# 05-USB-UART.net
KiCad netlist of a schematic drawn in Altium Designer
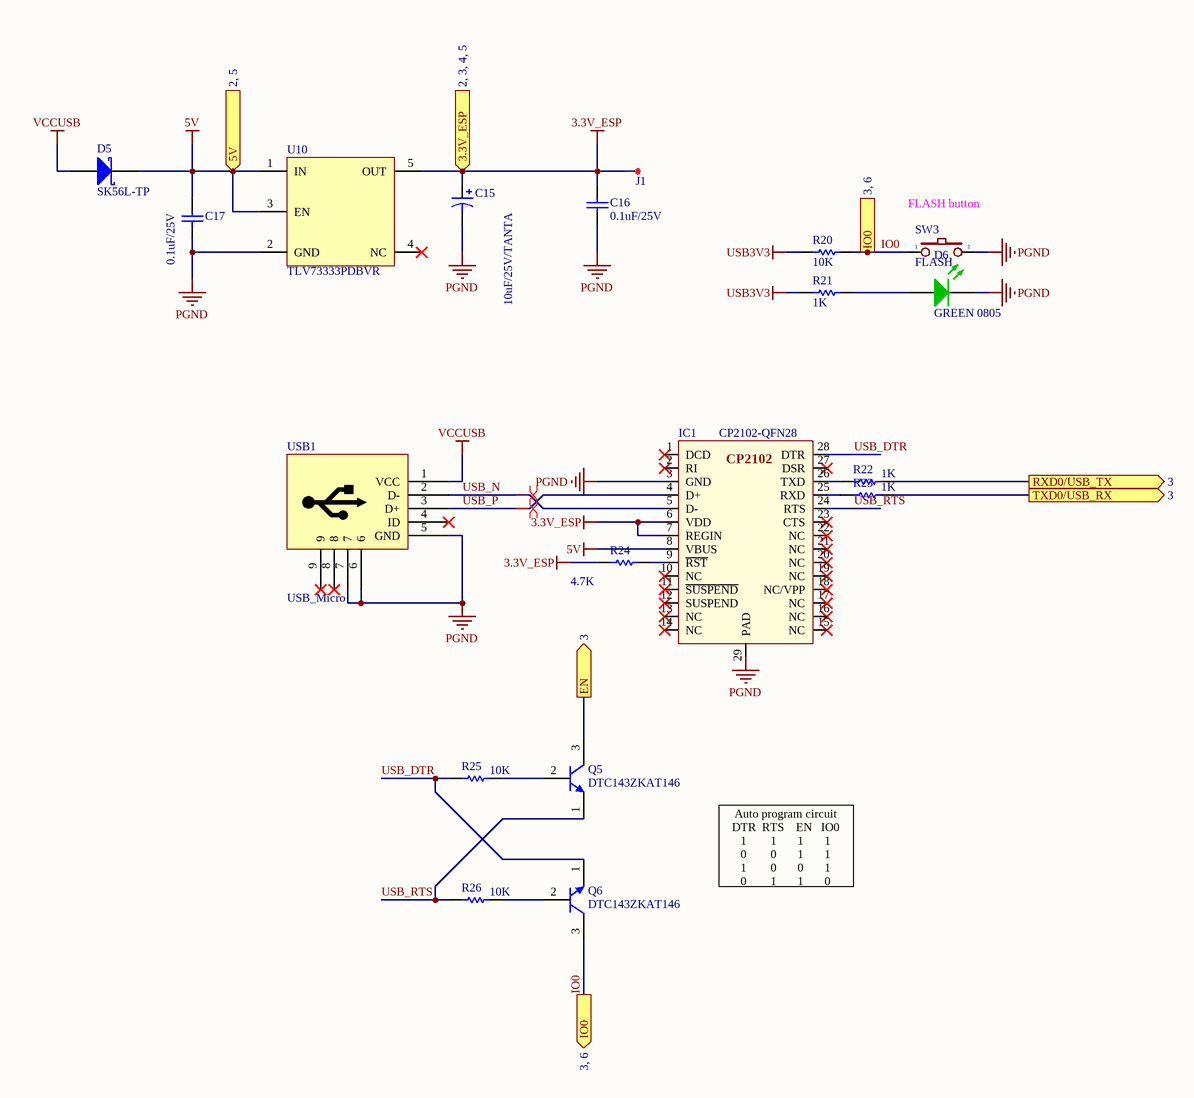
[diagram p0: 05-USB-UART.SchDoc]

(export (version "E")
  (design (tool "Eeschema 10.0.6"))
  (components
    (comp (ref "C15")
      (value "10uF/25V/TANTA")
      (footprint "CAP TANT CASE B SMD")
      (description "10µF Molded Tantalum Capacitors 25V 1411 (3528 Metric) 3 Ohm")
      (fields (field (name "MANUFACTURER") "KEMET"))
      (libsource (lib "GSHT_181013") (part "TAJB106M025RNJ"))
    )
    (comp (ref "C16")
      (value "0.1uF/25V")
      (footprint "CAP_CERA_C2012(CC0805INCH)")
      (description "0.1µF ±10% 25V Ceramic Capacitor X7R 0805 (2012 Metric)")
      (fields (field (name "MANUFACTURER") "KEMET"))
      (libsource (lib "GSHT_181013") (part "0.1uF/50V/C0603/10%"))
    )
    (comp (ref "C17")
      (value "0.1uF/25V")
      (footprint "CAP_CERA_C2012(CC0805INCH)")
      (description "0.1µF ±10% 25V Ceramic Capacitor X7R 0805 (2012 Metric)")
      (libsource (lib "GSHT_181013") (part "0.1uF/50V/C0603/10%"))
    )
    (comp (ref "D5")
      (value "SK56L-TP")
      (footprint "30# SK56L-TPMSCT-ND")
      (description "DIODE SCHOTTKY 60V 5A DO214AB")
      (libsource (lib "GSHT_181013") (part "30# SK56L-TP"))
    )
    (comp (ref "D6")
      (value "GREEN 0805")
      (footprint "Led 0805G")
      (description "Green 571nm LED Indication - Discrete 2V 0805 (2012 Metric)")
      (libsource (lib "GSHT_181013") (part "LED GREEN 0603"))
    )
    (comp (ref "IC1")
      (value "CP2102-QFN28")
      (footprint "CP2102-QFN28")
      (description "USB Bridge, USB to UART USB 2.0 UART Interface 28-QFN (5x5)")
      (libsource (lib "lpson") (part "CP2102"))
    )
    (comp (ref "J1")
      (value "TEST POINT")
      (footprint "TEST POINT 1mm")
      (description "TPoint")
      (libsource (lib "GSHT_181013") (part "PAD 1mm"))
    )
    (comp (ref "Q5")
      (value "DTC143ZKAT146")
      (footprint "6# DTC143ZKAT146-E")
      (description "Pre-Biased Bipolar Transistor (BJT) NPN - Pre-Biased 50V 100mA 250MHz 200mW Surface Mount SMT3")
      (libsource (lib "GSHT_181013") (part "6#DTC143ZKAT146"))
    )
    (comp (ref "Q6")
      (value "DTC143ZKAT146")
      (footprint "6# DTC143ZKAT146-E")
      (description "Pre-Biased Bipolar Transistor (BJT) NPN - Pre-Biased 50V 100mA 250MHz 200mW Surface Mount SMT3")
      (libsource (lib "GSHT_181013") (part "6#DTC143ZKAT146"))
    )
    (comp (ref "R20")
      (value "10K")
      (footprint "Res 0805 SMD")
      (description "10 kOhms ±1% 0.125W, 1/8W Chip Resistor 0805 (2012 Metric) Thick Film")
      (libsource (lib "GSHT_181013") (part "200K/R0603/1%"))
    )
    (comp (ref "R21")
      (value "1K")
      (footprint "Res 0805 SMD")
      (description "1 kOhms ±1% 0.125W, 1/8W Chip Resistor 0805 (2012 Metric) Automotive AEC-Q200 Thick Film")
      (libsource (lib "GSHT_181013") (part "200K/R0603/1%"))
    )
    (comp (ref "R22")
      (value "1K")
      (footprint "Res 0805 SMD")
      (description "1 kOhms ±1% 0.125W, 1/8W Chip Resistor 0805 (2012 Metric) Automotive AEC-Q200 Thick Film")
      (libsource (lib "GSHT_181013") (part "34.8K/R0805/1%"))
    )
    (comp (ref "R23")
      (value "1K")
      (footprint "Res 0805 SMD")
      (description "1 kOhms ±1% 0.125W, 1/8W Chip Resistor 0805 (2012 Metric) Automotive AEC-Q200 Thick Film")
      (libsource (lib "GSHT_181013") (part "34.8K/R0805/1%"))
    )
    (comp (ref "R24")
      (value "4.7K")
      (footprint "Res 0805 SMD")
      (description "4.7 kOhms ±1% 0.125W, 1/8W Chip Resistor 0805 (2012 Metric) Thick Film")
      (libsource (lib "GSHT_181013") (part "34.8K/R0805/1%"))
    )
    (comp (ref "R25")
      (value "10K")
      (footprint "Res 0805 SMD")
      (description "10 kOhms ±1% 0.125W, 1/8W Chip Resistor 0805 (2012 Metric) Thick Film")
      (libsource (lib "GSHT_181013") (part "34.8K/R0805/1%"))
    )
    (comp (ref "R26")
      (value "10K")
      (footprint "Res 0805 SMD")
      (description "10 kOhms ±1% 0.125W, 1/8W Chip Resistor 0805 (2012 Metric) Thick Film")
      (libsource (lib "GSHT_181013") (part "34.8K/R0805/1%"))
    )
    (comp (ref "SW3")
      (value "FLASH")
      (footprint "Button 3x4mm")
      (description "SWITCH TACTILE SPST-NO 0.05A 12V")
      (libsource (lib "lpson") (part "SW2"))
    )
    (comp (ref "U10")
      (value "TLV73333PDBVR")
      (footprint "20# TLV73333PDBVR")
      (description "Linear Voltage Regulator IC Positive Fixed 1 Output 3.3V 300mA SOT-23-5")
      (libsource (lib "GSHT_181013") (part "20#TLV73333PDBVR"))
    )
    (comp (ref "USB1")
      (value "USB_Micro")
      (footprint "USB_MICRO_B - Digikey")
      (description "USB - micro B USB 2.0 Receptacle Connector 5 Position Surface Mount, Right Angle; Through Hole")
      (libsource (lib "lpson") (part "USB_MINI"))
    )
  )
  (nets
    (net (code "1") (name "/EN") (class "Default")
      (node (ref "Q5") (pin "3") (pinfunction "C_3") (pintype "passive"))
    )
    (net (code "2") (name "/IO0") (class "Default")
      (node (ref "Q6") (pin "3") (pinfunction "C_3") (pintype "passive"))
      (node (ref "R20") (pin "2") (pinfunction "2_2") (pintype "passive"))
      (node (ref "SW3") (pin "1") (pinfunction "1_1") (pintype "passive"))
    )
    (net (code "3") (name "/RXD0{slash}USB_TX") (class "Default")
      (node (ref "R22") (pin "1") (pinfunction "1_1") (pintype "passive"))
    )
    (net (code "4") (name "/TXD0{slash}USB_RX") (class "Default")
      (node (ref "R23") (pin "1") (pinfunction "1_1") (pintype "passive"))
    )
    (net (code "5") (name "/USB_DTR") (class "Default")
      (node (ref "IC1") (pin "28") (pinfunction "DTR_28") (pintype "passive"))
      (node (ref "Q6") (pin "1") (pinfunction "E_1") (pintype "passive"))
      (node (ref "R25") (pin "2") (pinfunction "2_2") (pintype "passive"))
    )
    (net (code "6") (name "/USB_N") (class "Default")
      (node (ref "IC1") (pin "5") (pinfunction "D-_5") (pintype "passive"))
      (node (ref "USB1") (pin "2") (pinfunction "D-_2") (pintype "passive"))
    )
    (net (code "7") (name "/USB_P") (class "Default")
      (node (ref "IC1") (pin "4") (pinfunction "D+_4") (pintype "passive"))
      (node (ref "USB1") (pin "3") (pinfunction "D+_3") (pintype "passive"))
    )
    (net (code "8") (name "/USB_RTS") (class "Default")
      (node (ref "IC1") (pin "24") (pinfunction "RTS_24") (pintype "passive"))
      (node (ref "Q5") (pin "1") (pinfunction "E_1") (pintype "passive"))
      (node (ref "R26") (pin "2") (pinfunction "2_2") (pintype "passive"))
    )
    (net (code "9") (name "3.3V_ESP") (class "Default")
      (node (ref "C15") (pin "1") (pinfunction "1_1") (pintype "passive"))
      (node (ref "C16") (pin "2") (pinfunction "2_2") (pintype "passive"))
      (node (ref "IC1") (pin "6") (pinfunction "VDD_6") (pintype "passive"))
      (node (ref "IC1") (pin "7") (pinfunction "REGIN_7") (pintype "passive"))
      (node (ref "J1") (pin "1") (pinfunction "TP_1") (pintype "passive"))
      (node (ref "R24") (pin "1") (pinfunction "1_1") (pintype "passive"))
      (node (ref "U10") (pin "5") (pinfunction "OUT_5") (pintype "passive"))
    )
    (net (code "10") (name "5V") (class "Default")
      (node (ref "C17") (pin "2") (pinfunction "2_2") (pintype "passive"))
      (node (ref "D5") (pin "2") (pinfunction "K_2") (pintype "passive"))
      (node (ref "IC1") (pin "8") (pinfunction "VBUS_8") (pintype "passive"))
      (node (ref "U10") (pin "1") (pinfunction "IN_1") (pintype "passive"))
      (node (ref "U10") (pin "3") (pinfunction "EN_3") (pintype "passive"))
    )
    (net (code "11") (name "Net-(D6-A)") (class "Default")
      (node (ref "D6") (pin "1") (pinfunction "A_1") (pintype "passive"))
      (node (ref "R21") (pin "2") (pinfunction "2_2") (pintype "passive"))
    )
    (net (code "12") (name "Net-(IC1-RXD)") (class "Default")
      (node (ref "IC1") (pin "25") (pinfunction "RXD_25") (pintype "passive"))
      (node (ref "R23") (pin "2") (pinfunction "2_2") (pintype "passive"))
    )
    (net (code "13") (name "Net-(IC1-TXD)") (class "Default")
      (node (ref "IC1") (pin "26") (pinfunction "TXD_26") (pintype "passive"))
      (node (ref "R22") (pin "2") (pinfunction "2_2") (pintype "passive"))
    )
    (net (code "14") (name "Net-(IC1-~{RST})") (class "Default")
      (node (ref "IC1") (pin "9") (pinfunction "~{RST}_9") (pintype "passive"))
      (node (ref "R24") (pin "2") (pinfunction "2_2") (pintype "passive"))
    )
    (net (code "15") (name "Net-(Q5-B)") (class "Default")
      (node (ref "Q5") (pin "2") (pinfunction "B_2") (pintype "passive"))
      (node (ref "R25") (pin "1") (pinfunction "1_1") (pintype "passive"))
    )
    (net (code "16") (name "Net-(Q6-B)") (class "Default")
      (node (ref "Q6") (pin "2") (pinfunction "B_2") (pintype "passive"))
      (node (ref "R26") (pin "1") (pinfunction "1_1") (pintype "passive"))
    )
    (net (code "17") (name "PGND") (class "Default")
      (node (ref "C15") (pin "2") (pinfunction "2_2") (pintype "passive"))
      (node (ref "C16") (pin "1") (pinfunction "1_1") (pintype "passive"))
      (node (ref "C17") (pin "1") (pinfunction "1_1") (pintype "passive"))
      (node (ref "D6") (pin "2") (pinfunction "K_2") (pintype "passive"))
      (node (ref "IC1") (pin "29") (pinfunction "PAD_29") (pintype "passive"))
      (node (ref "IC1") (pin "3") (pinfunction "GND_3") (pintype "passive"))
      (node (ref "SW3") (pin "2") (pinfunction "2_2") (pintype "passive"))
      (node (ref "U10") (pin "2") (pinfunction "GND_2") (pintype "passive"))
      (node (ref "USB1") (pin "5") (pinfunction "GND_5") (pintype "passive"))
      (node (ref "USB1") (pin "6") (pinfunction "6_6") (pintype "passive"))
      (node (ref "USB1") (pin "7") (pinfunction "7_7") (pintype "passive"))
    )
    (net (code "18") (name "USB3V3") (class "Default")
      (node (ref "R20") (pin "1") (pinfunction "1_1") (pintype "passive"))
      (node (ref "R21") (pin "1") (pinfunction "1_1") (pintype "passive"))
    )
    (net (code "19") (name "VCCUSB") (class "Default")
      (node (ref "D5") (pin "1") (pinfunction "A_1") (pintype "passive"))
      (node (ref "USB1") (pin "1") (pinfunction "VCC_1") (pintype "passive"))
    )
    (net (code "20") (name "unconnected-(IC1-CTS-Pad23)") (class "Default")
      (node (ref "IC1") (pin "23") (pinfunction "CTS_23") (pintype "passive+no_connect"))
    )
    (net (code "21") (name "unconnected-(IC1-DCD-Pad1)") (class "Default")
      (node (ref "IC1") (pin "1") (pinfunction "DCD_1") (pintype "passive+no_connect"))
    )
    (net (code "22") (name "unconnected-(IC1-DSR-Pad27)") (class "Default")
      (node (ref "IC1") (pin "27") (pinfunction "DSR_27") (pintype "passive+no_connect"))
    )
    (net (code "23") (name "unconnected-(IC1-NC-Pad10)") (class "Default")
      (node (ref "IC1") (pin "10") (pinfunction "NC_10") (pintype "passive+no_connect"))
    )
    (net (code "24") (name "unconnected-(IC1-NC-Pad13)") (class "Default")
      (node (ref "IC1") (pin "13") (pinfunction "NC_13") (pintype "passive+no_connect"))
    )
    (net (code "25") (name "unconnected-(IC1-NC-Pad14)") (class "Default")
      (node (ref "IC1") (pin "14") (pinfunction "NC_14") (pintype "passive+no_connect"))
    )
    (net (code "26") (name "unconnected-(IC1-NC-Pad15)") (class "Default")
      (node (ref "IC1") (pin "15") (pinfunction "NC_15") (pintype "passive+no_connect"))
    )
    (net (code "27") (name "unconnected-(IC1-NC-Pad16)") (class "Default")
      (node (ref "IC1") (pin "16") (pinfunction "NC_16") (pintype "passive+no_connect"))
    )
    (net (code "28") (name "unconnected-(IC1-NC-Pad17)") (class "Default")
      (node (ref "IC1") (pin "17") (pinfunction "NC_17") (pintype "passive+no_connect"))
    )
    (net (code "29") (name "unconnected-(IC1-NC-Pad19)") (class "Default")
      (node (ref "IC1") (pin "19") (pinfunction "NC_19") (pintype "passive+no_connect"))
    )
    (net (code "30") (name "unconnected-(IC1-NC-Pad20)") (class "Default")
      (node (ref "IC1") (pin "20") (pinfunction "NC_20") (pintype "passive+no_connect"))
    )
    (net (code "31") (name "unconnected-(IC1-NC-Pad21)") (class "Default")
      (node (ref "IC1") (pin "21") (pinfunction "NC_21") (pintype "passive+no_connect"))
    )
    (net (code "32") (name "unconnected-(IC1-NC-Pad22)") (class "Default")
      (node (ref "IC1") (pin "22") (pinfunction "NC_22") (pintype "passive+no_connect"))
    )
    (net (code "33") (name "unconnected-(IC1-NC{slash}VPP-Pad18)") (class "Default")
      (node (ref "IC1") (pin "18") (pinfunction "NC/VPP_18") (pintype "passive+no_connect"))
    )
    (net (code "34") (name "unconnected-(IC1-RI-Pad2)") (class "Default")
      (node (ref "IC1") (pin "2") (pinfunction "RI_2") (pintype "passive+no_connect"))
    )
    (net (code "35") (name "unconnected-(IC1-SUSPEND-Pad12)") (class "Default")
      (node (ref "IC1") (pin "12") (pinfunction "SUSPEND_12") (pintype "passive+no_connect"))
    )
    (net (code "36") (name "unconnected-(IC1-~{SUSPEND}-Pad11)") (class "Default")
      (node (ref "IC1") (pin "11") (pinfunction "~{SUSPEND}_11") (pintype "passive+no_connect"))
    )
    (net (code "37") (name "unconnected-(U10-NC-Pad4)") (class "Default")
      (node (ref "U10") (pin "4") (pinfunction "NC_4") (pintype "passive+no_connect"))
    )
    (net (code "38") (name "unconnected-(USB1-ID-Pad4)") (class "Default")
      (node (ref "USB1") (pin "4") (pinfunction "ID_4") (pintype "passive+no_connect"))
    )
    (net (code "39") (name "unconnected-(USB1-Pad8)") (class "Default")
      (node (ref "USB1") (pin "8") (pinfunction "8_8") (pintype "passive+no_connect"))
    )
    (net (code "40") (name "unconnected-(USB1-Pad9)") (class "Default")
      (node (ref "USB1") (pin "9") (pinfunction "9_9") (pintype "passive+no_connect"))
    )
  )
)
